# Musical_Grasping_Training_Aid_Schematic.net
KiCad netlist of a schematic drawn in EAGLE
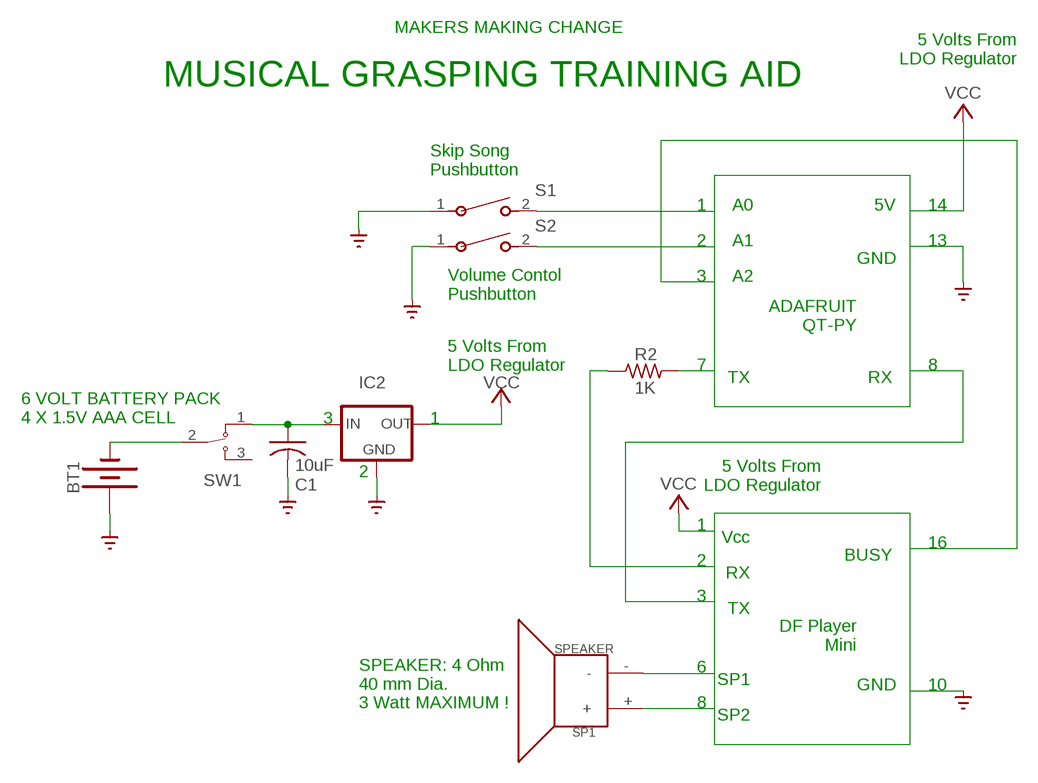
[diagram p0: schematic, sheet 1]

(export (version "E")
  (design (tool "Eeschema 10.0.6"))
  (components
    (comp (ref "BT1")
      (value "BATTERY-AAA")
      (footprint "eagle-import:BATTERY-AAA")
      (libsource (lib "eagle-import") (part "BATTERY-AAA"))
    )
    (comp (ref "C1")
      (value "10uF")
      (footprint "eagle-import:C025-025X050")
      (libsource (lib "eagle-import") (part "C-US025-025X050"))
    )
    (comp (ref "IC2")
      (value "78LXX")
      (footprint "eagle-import:78LXX")
      (libsource (lib "eagle-import") (part "78LXX"))
    )
    (comp (ref "R2")
      (value "1K")
      (footprint "eagle-import:0204_7")
      (libsource (lib "eagle-import") (part "R-US_0204/7"))
    )
    (comp (ref "S1")
      (value "1825966-1")
      (footprint "eagle-import:SWDIP2_256X170P100")
      (fields (field (name "COPYRIGHT") "Copyright (C) 2016 Accelerated Designs. All rights reserved"))
      (libsource (lib "eagle-import") (part "1825966-1"))
    )
    (comp (ref "S2")
      (value "1825966-1")
      (footprint "eagle-import:SWDIP2_256X170P100")
      (fields (field (name "COPYRIGHT") "Copyright (C) 2016 Accelerated Designs. All rights reserved"))
      (libsource (lib "eagle-import") (part "1825966-1"))
    )
    (comp (ref "SP1")
      (value "SPEAKER")
      (footprint "eagle-import:PCB_MOUNT_SPEAKER")
      (libsource (lib "eagle-import") (part "SPEAKER"))
    )
    (comp (ref "SW1")
      (value "ATE1E-2M3-10-Z")
      (footprint "eagle-import:ATE1E-2M3-10-Z")
      (fields
        (field (name "DIGIKEY_PARTNO") "563-1159-ND")
        (field (name "MANUFACTURER") "Nidec Copal Electronics")
        (field (name "CREATED_BY") "PCBLayout.com")
      )
      (libsource (lib "eagle-import") (part "ATE1E-2M3-10-Z"))
    )
  )
  (nets
    (net (code "1") (name "Net-(BT1--)") (class "Default")
      (node (ref "BT1") (pin "GND@1") (pinfunction "-_GND@1") (pintype "power_in"))
      (node (ref "SW1") (pin "2") (pinfunction "2_2") (pintype "passive"))
    )
    (net (code "2") (name "Net-(C1-Pad1)") (class "Default")
      (node (ref "C1") (pin "1") (pinfunction "1_1") (pintype "passive"))
      (node (ref "IC2") (pin "IN") (pinfunction "IN_IN") (pintype "input"))
      (node (ref "SW1") (pin "1") (pinfunction "1_1") (pintype "passive"))
    )
    (net (code "3") (name "Net-(SP1-Pad+)") (class "Default")
      (node (ref "SP1") (pin "+") (pinfunction "+_+") (pintype "bidirectional"))
      (node (ref "SP1") (pin "-") (pinfunction "-_-") (pintype "bidirectional"))
    )
    (net (code "4") (name "SUPPLY0_GND_") (class "Default")
      (node (ref "BT1") (pin "PWR@1") (pinfunction "+_PWR@1") (pintype "power_in"))
      (node (ref "C1") (pin "2") (pinfunction "2_2") (pintype "passive"))
      (node (ref "IC2") (pin "GND") (pinfunction "GND_GND") (pintype "input"))
      (node (ref "S1") (pin "1") (pinfunction "1_1") (pintype "passive"))
      (node (ref "S2") (pin "1") (pinfunction "1_1") (pintype "passive"))
    )
    (net (code "5") (name "VCC") (class "Default")
      (node (ref "IC2") (pin "OUT") (pinfunction "OUT_OUT") (pintype "passive"))
    )
    (net (code "6") (name "unconnected-(R2-Pad1)") (class "Default")
      (node (ref "R2") (pin "1") (pinfunction "1_1") (pintype "passive"))
    )
    (net (code "7") (name "unconnected-(R2-Pad2)") (class "Default")
      (node (ref "R2") (pin "2") (pinfunction "2_2") (pintype "passive"))
    )
    (net (code "8") (name "unconnected-(S1-Pad2)") (class "Default")
      (node (ref "S1") (pin "2") (pinfunction "2_2") (pintype "passive"))
    )
    (net (code "9") (name "unconnected-(S2-Pad2)") (class "Default")
      (node (ref "S2") (pin "2") (pinfunction "2_2") (pintype "passive"))
    )
    (net (code "10") (name "unconnected-(SW1-Pad3)") (class "Default")
      (node (ref "SW1") (pin "3") (pinfunction "3_3") (pintype "passive"))
    )
  )
)
